# IoTMainBoard.net
KiCad netlist of a schematic drawn in Altium Designer
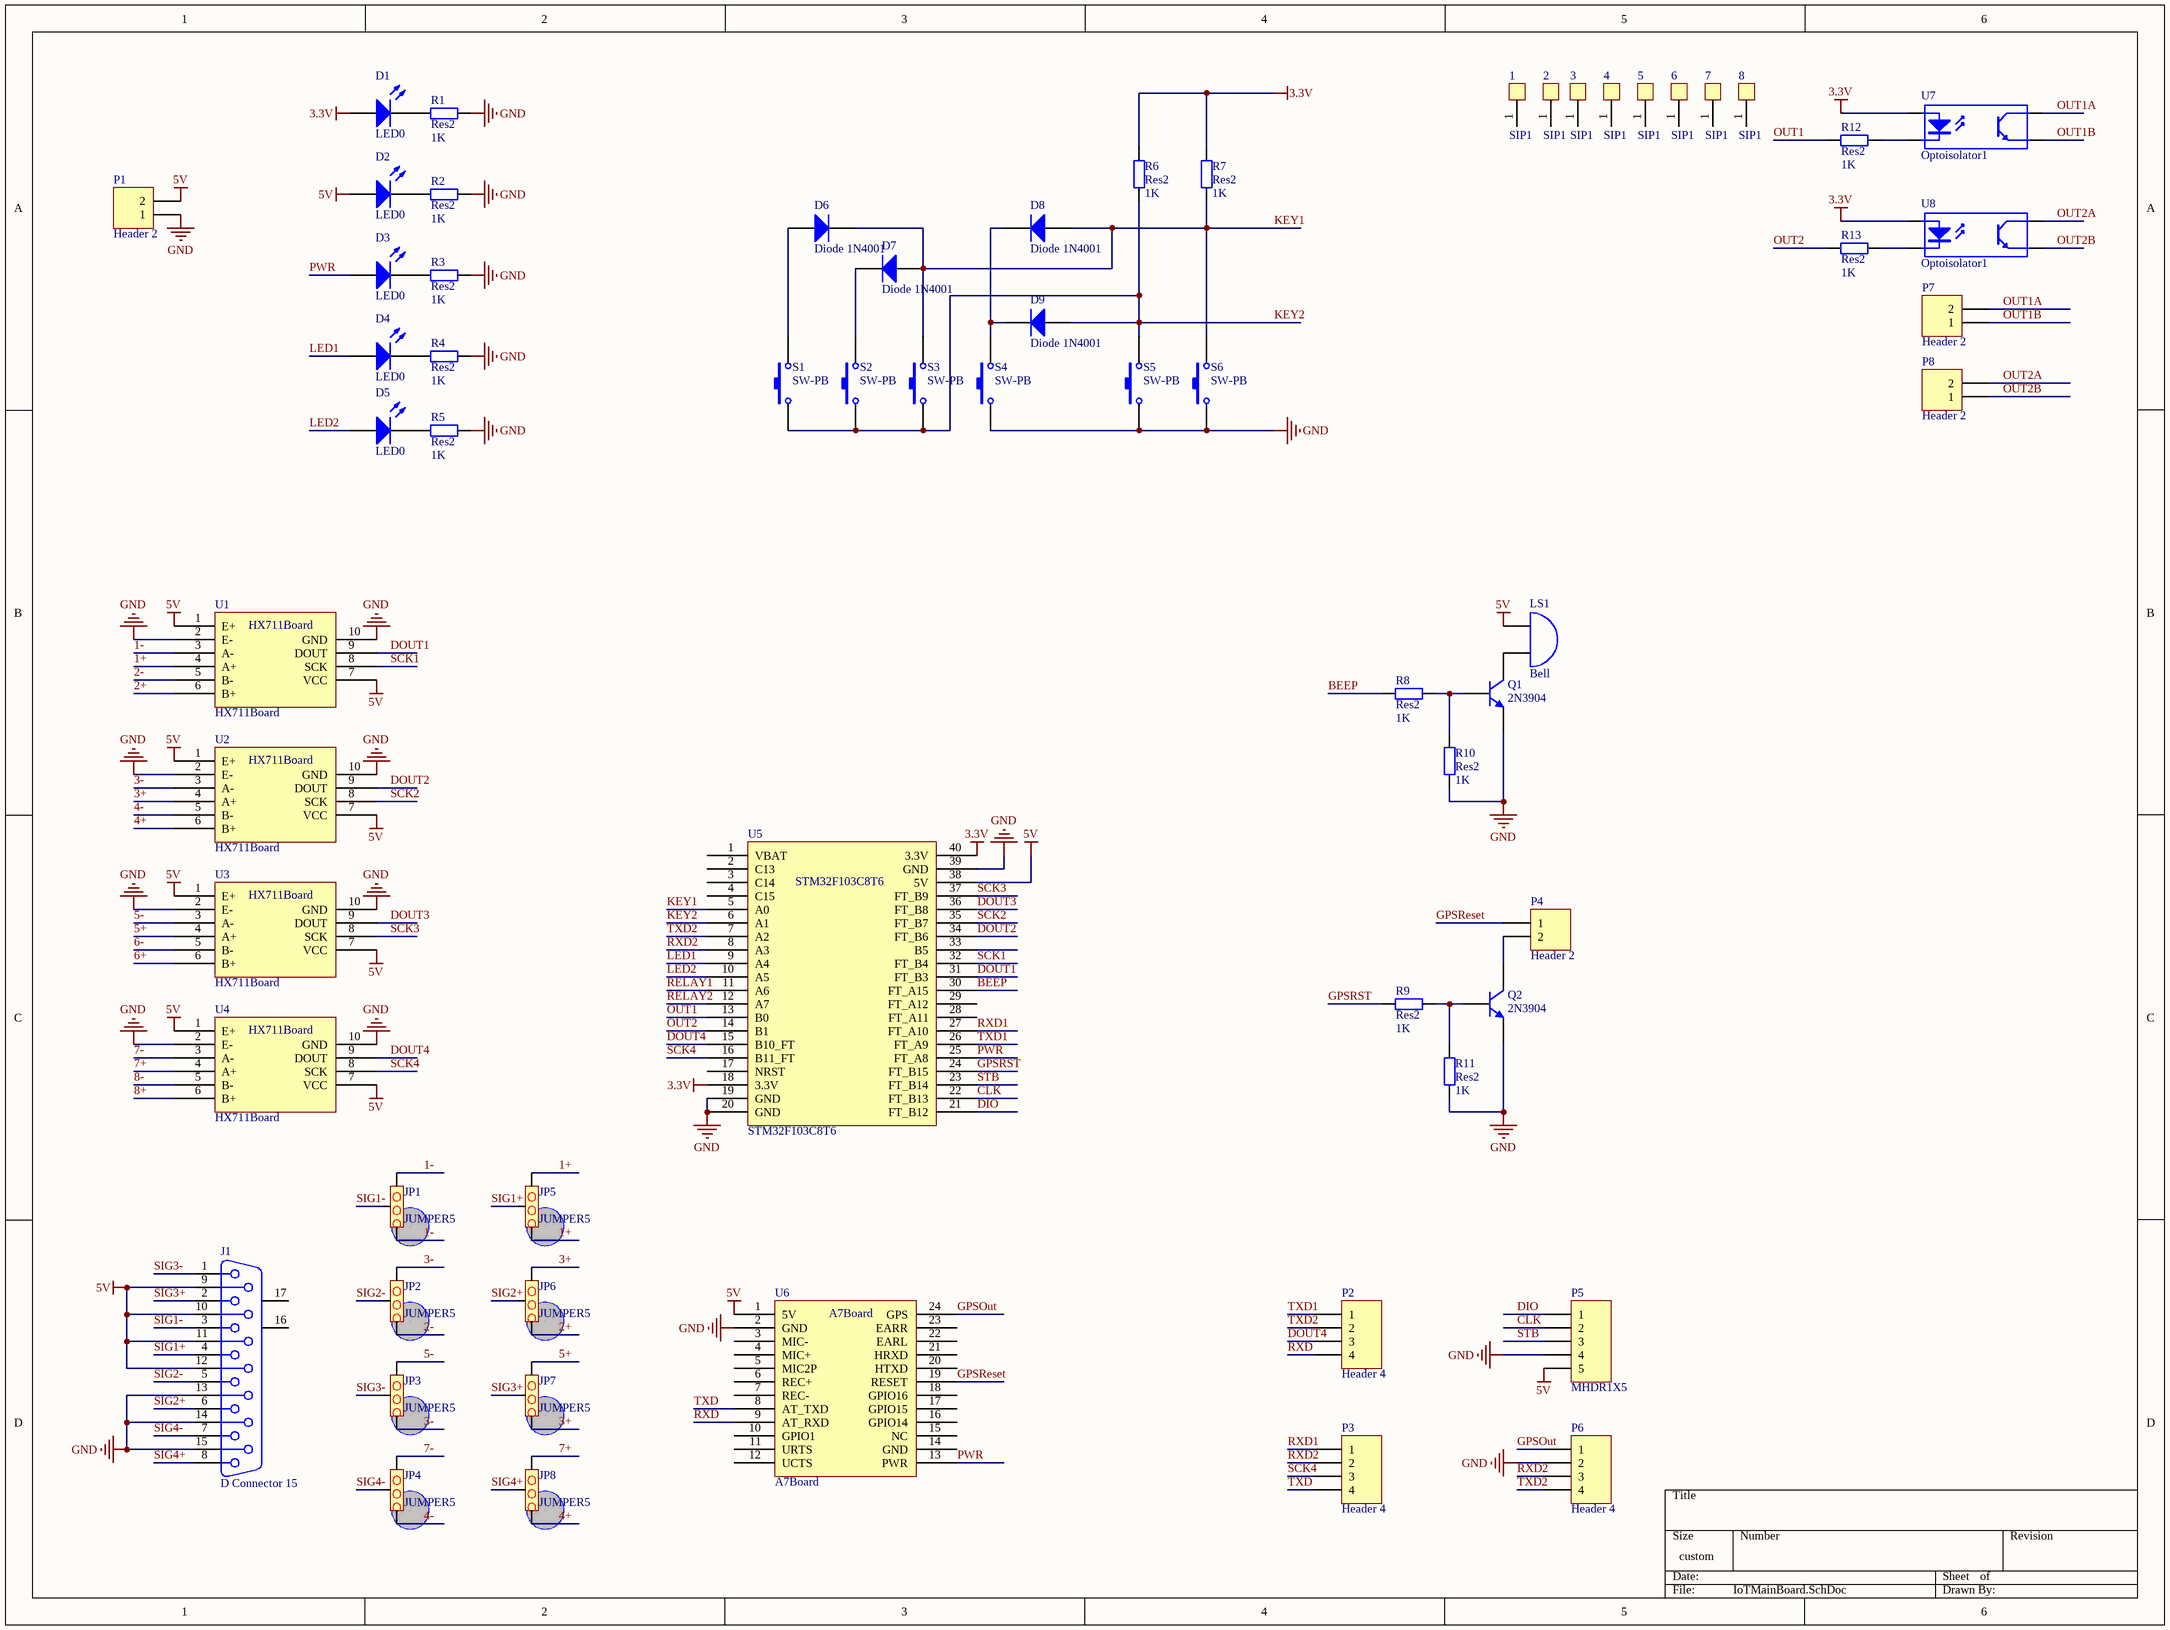
[diagram p0: IoTMainBoard.SchDoc]

(export (version "E")
  (design (tool "Eeschema 10.0.6"))
  (components
    (comp (ref "1")
      (value "SIP1")
      (footprint "hole")
      (description "Variable Resistor")
      (fields (field (name "PUBLISHER") "Altium Limited"))
      (libsource (lib "jointbar") (part "SIP1"))
    )
    (comp (ref "2")
      (value "SIP1")
      (footprint "hole")
      (description "Variable Resistor")
      (fields (field (name "PUBLISHER") "Altium Limited"))
      (libsource (lib "jointbar") (part "SIP1"))
    )
    (comp (ref "3")
      (value "SIP1")
      (footprint "hole")
      (description "Variable Resistor")
      (fields (field (name "PUBLISHER") "Altium Limited"))
      (libsource (lib "jointbar") (part "SIP1"))
    )
    (comp (ref "4")
      (value "SIP1")
      (footprint "hole")
      (description "Variable Resistor")
      (fields (field (name "PUBLISHER") "Altium Limited"))
      (libsource (lib "jointbar") (part "SIP1"))
    )
    (comp (ref "5")
      (value "SIP1")
      (footprint "hole")
      (description "Variable Resistor")
      (fields (field (name "PUBLISHER") "Altium Limited"))
      (libsource (lib "jointbar") (part "SIP1"))
    )
    (comp (ref "6")
      (value "SIP1")
      (footprint "hole")
      (description "Variable Resistor")
      (fields (field (name "PUBLISHER") "Altium Limited"))
      (libsource (lib "jointbar") (part "SIP1"))
    )
    (comp (ref "7")
      (value "SIP1")
      (footprint "hole")
      (description "Variable Resistor")
      (fields (field (name "PUBLISHER") "Altium Limited"))
      (libsource (lib "jointbar") (part "SIP1"))
    )
    (comp (ref "8")
      (value "SIP1")
      (footprint "hole")
      (description "Variable Resistor")
      (fields (field (name "PUBLISHER") "Altium Limited"))
      (libsource (lib "jointbar") (part "SIP1"))
    )
    (comp (ref "D1")
      (value "LED0")
      (footprint "LED0")
      (description "Typical INFRARED GaAs LED")
      (fields (field (name "PUBLISHER") "Altium Limited"))
      (libsource (lib "Miscellaneous Devices") (part "LED0"))
    )
    (comp (ref "D2")
      (value "LED0")
      (footprint "LED0")
      (description "Typical INFRARED GaAs LED")
      (fields (field (name "PUBLISHER") "Altium Limited"))
      (libsource (lib "Miscellaneous Devices") (part "LED0"))
    )
    (comp (ref "D3")
      (value "LED0")
      (footprint "LED0")
      (description "Typical INFRARED GaAs LED")
      (fields (field (name "PUBLISHER") "Altium Limited"))
      (libsource (lib "Miscellaneous Devices") (part "LED0"))
    )
    (comp (ref "D4")
      (value "LED0")
      (footprint "LED0")
      (description "Typical INFRARED GaAs LED")
      (fields (field (name "PUBLISHER") "Altium Limited"))
      (libsource (lib "Miscellaneous Devices") (part "LED0"))
    )
    (comp (ref "D5")
      (value "LED0")
      (footprint "LED0")
      (description "Typical INFRARED GaAs LED")
      (fields (field (name "PUBLISHER") "Altium Limited"))
      (libsource (lib "Miscellaneous Devices") (part "LED0"))
    )
    (comp (ref "D6")
      (value "Diode 1N4001")
      (footprint "1N4148")
      (description "1 Amp General Purpose Rectifier")
      (fields (field (name "PUBLISHER") "Altium Limited"))
      (libsource (lib "Miscellaneous Devices") (part "Diode 1N4001"))
    )
    (comp (ref "D7")
      (value "Diode 1N4001")
      (footprint "1N4148")
      (description "1 Amp General Purpose Rectifier")
      (fields (field (name "PUBLISHER") "Altium Limited"))
      (libsource (lib "Miscellaneous Devices") (part "Diode 1N4001"))
    )
    (comp (ref "D8")
      (value "Diode 1N4001")
      (footprint "1N4148")
      (description "1 Amp General Purpose Rectifier")
      (fields (field (name "PUBLISHER") "Altium Limited"))
      (libsource (lib "Miscellaneous Devices") (part "Diode 1N4001"))
    )
    (comp (ref "D9")
      (value "Diode 1N4001")
      (footprint "1N4148")
      (description "1 Amp General Purpose Rectifier")
      (fields (field (name "PUBLISHER") "Altium Limited"))
      (libsource (lib "Miscellaneous Devices") (part "Diode 1N4001"))
    )
    (comp (ref "J1")
      (value "D Connector 15")
      (footprint "DB15F_DB")
      (description "Receptacle Assembly, 15 Position, Right Angle")
      (fields (field (name "PUBLISHER") "Altium Limited"))
      (libsource (lib "Miscellaneous Connectors") (part "D Connector 15"))
    )
    (comp (ref "JP1") (value "JUMPER5") (footprint "CON3") (libsource (lib "jointbar") (part "JUMPER5")))
    (comp (ref "JP2") (value "JUMPER5") (footprint "CON3") (libsource (lib "jointbar") (part "JUMPER5")))
    (comp (ref "JP3") (value "JUMPER5") (footprint "CON3") (libsource (lib "jointbar") (part "JUMPER5")))
    (comp (ref "JP4") (value "JUMPER5") (footprint "CON3") (libsource (lib "jointbar") (part "JUMPER5")))
    (comp (ref "JP5") (value "JUMPER5") (footprint "CON3") (libsource (lib "jointbar") (part "JUMPER5")))
    (comp (ref "JP6") (value "JUMPER5") (footprint "CON3") (libsource (lib "jointbar") (part "JUMPER5")))
    (comp (ref "JP7") (value "JUMPER5") (footprint "CON3") (libsource (lib "jointbar") (part "JUMPER5")))
    (comp (ref "JP8") (value "JUMPER5") (footprint "CON3") (libsource (lib "jointbar") (part "JUMPER5")))
    (comp (ref "LS1")
      (value "Bell")
      (footprint "BEEP")
      (description "Electrical Bell")
      (fields (field (name "PUBLISHER") "Altium Limited"))
      (libsource (lib "Miscellaneous Devices") (part "Bell"))
    )
    (comp (ref "P1")
      (value "Header 2")
      (footprint "Power2")
      (description "Header, 2-Pin")
      (fields (field (name "PUBLISHER") "Altium Limited"))
      (libsource (lib "Miscellaneous Connectors") (part "Header 2"))
    )
    (comp (ref "P2")
      (value "Header 4")
      (footprint "JUMP3")
      (description "Header, 4-Pin")
      (fields (field (name "PUBLISHER") "Altium Limited"))
      (libsource (lib "Miscellaneous Connectors") (part "Header 4"))
    )
    (comp (ref "P3")
      (value "Header 4")
      (footprint "JUMP3")
      (description "Header, 4-Pin")
      (fields (field (name "PUBLISHER") "Altium Limited"))
      (libsource (lib "Miscellaneous Connectors") (part "Header 4"))
    )
    (comp (ref "P4")
      (value "Header 2")
      (footprint "HDR1X2")
      (description "Header, 2-Pin")
      (fields (field (name "PUBLISHER") "Altium Limited"))
      (libsource (lib "") (part "Header 2_1"))
    )
    (comp (ref "P5")
      (value "MHDR1X5")
      (footprint "HDR1X5")
      (description "Header, 5-Pin")
      (fields (field (name "PUBLISHER") "Altium Limited"))
      (libsource (lib "Miscellaneous Connectors") (part "MHDR1X5"))
    )
    (comp (ref "P6")
      (value "Header 4")
      (footprint "HDR1X4")
      (description "Header, 4-Pin")
      (fields (field (name "PUBLISHER") "Altium Limited"))
      (libsource (lib "Miscellaneous Connectors") (part "Header 4"))
    )
    (comp (ref "P7")
      (value "Header 2")
      (footprint "HDR1X2")
      (description "Header, 2-Pin")
      (fields (field (name "PUBLISHER") "Altium Limited"))
      (libsource (lib "Miscellaneous Connectors") (part "Header 2"))
    )
    (comp (ref "P8")
      (value "Header 2")
      (footprint "HDR1X2")
      (description "Header, 2-Pin")
      (fields (field (name "PUBLISHER") "Altium Limited"))
      (libsource (lib "Miscellaneous Connectors") (part "Header 2"))
    )
    (comp (ref "Q1")
      (value "2N3904")
      (footprint "SOT-23")
      (description "NPN General Purpose Amplifier")
      (fields (field (name "PUBLISHER") "Altium Limited"))
      (libsource (lib "Miscellaneous Devices") (part "2N3904"))
    )
    (comp (ref "Q2")
      (value "2N3904")
      (footprint "SOT-23")
      (description "NPN General Purpose Amplifier")
      (fields (field (name "PUBLISHER") "Altium Limited"))
      (libsource (lib "Miscellaneous Devices") (part "2N3904"))
    )
    (comp (ref "R1")
      (value "Res2")
      (footprint "0805")
      (description "Resistor")
      (fields (field (name "ALTIUM_VALUE") "1K") (field (name "PUBLISHER") "Altium Limited"))
      (libsource (lib "") (part "Res2_2"))
    )
    (comp (ref "R2")
      (value "Res2")
      (footprint "0805")
      (description "Resistor")
      (fields (field (name "ALTIUM_VALUE") "1K") (field (name "PUBLISHER") "Altium Limited"))
      (libsource (lib "") (part "Res2_2"))
    )
    (comp (ref "R3")
      (value "Res2")
      (footprint "0805")
      (description "Resistor")
      (fields (field (name "ALTIUM_VALUE") "1K") (field (name "PUBLISHER") "Altium Limited"))
      (libsource (lib "") (part "Res2_2"))
    )
    (comp (ref "R4")
      (value "Res2")
      (footprint "0805")
      (description "Resistor")
      (fields (field (name "ALTIUM_VALUE") "1K") (field (name "PUBLISHER") "Altium Limited"))
      (libsource (lib "") (part "Res2_2"))
    )
    (comp (ref "R5")
      (value "Res2")
      (footprint "0805")
      (description "Resistor")
      (fields (field (name "ALTIUM_VALUE") "1K") (field (name "PUBLISHER") "Altium Limited"))
      (libsource (lib "") (part "Res2_2"))
    )
    (comp (ref "R6")
      (value "Res2")
      (footprint "0805")
      (description "Resistor")
      (fields (field (name "ALTIUM_VALUE") "1K") (field (name "PUBLISHER") "Altium Limited"))
      (libsource (lib "Miscellaneous Devices") (part "Res2"))
    )
    (comp (ref "R7")
      (value "Res2")
      (footprint "0805")
      (description "Resistor")
      (fields (field (name "ALTIUM_VALUE") "1K") (field (name "PUBLISHER") "Altium Limited"))
      (libsource (lib "Miscellaneous Devices") (part "Res2"))
    )
    (comp (ref "R8")
      (value "Res2")
      (footprint "0805")
      (description "Resistor")
      (fields (field (name "ALTIUM_VALUE") "1K") (field (name "PUBLISHER") "Altium Limited"))
      (libsource (lib "") (part "Res2_2"))
    )
    (comp (ref "R9")
      (value "Res2")
      (footprint "0805")
      (description "Resistor")
      (fields (field (name "ALTIUM_VALUE") "1K") (field (name "PUBLISHER") "Altium Limited"))
      (libsource (lib "") (part "Res2_2"))
    )
    (comp (ref "R10")
      (value "Res2")
      (footprint "0805")
      (description "Resistor")
      (fields (field (name "ALTIUM_VALUE") "1K") (field (name "PUBLISHER") "Altium Limited"))
      (libsource (lib "") (part "Res2_1"))
    )
    (comp (ref "R11")
      (value "Res2")
      (footprint "0805")
      (description "Resistor")
      (fields (field (name "ALTIUM_VALUE") "1K") (field (name "PUBLISHER") "Altium Limited"))
      (libsource (lib "") (part "Res2_1"))
    )
    (comp (ref "R12")
      (value "Res2")
      (footprint "0805")
      (description "Resistor")
      (fields (field (name "ALTIUM_VALUE") "1K") (field (name "PUBLISHER") "Altium Limited"))
      (libsource (lib "") (part "Res2_3"))
    )
    (comp (ref "R13")
      (value "Res2")
      (footprint "0805")
      (description "Resistor")
      (fields (field (name "ALTIUM_VALUE") "1K") (field (name "PUBLISHER") "Altium Limited"))
      (libsource (lib "") (part "Res2_3"))
    )
    (comp (ref "S1")
      (value "SW-PB")
      (footprint "KEY1")
      (description "Switch")
      (fields (field (name "PUBLISHER") "Altium Limited"))
      (libsource (lib "Miscellaneous Devices") (part "SW-PB"))
    )
    (comp (ref "S2")
      (value "SW-PB")
      (footprint "KEY1")
      (description "Switch")
      (fields (field (name "PUBLISHER") "Altium Limited"))
      (libsource (lib "Miscellaneous Devices") (part "SW-PB"))
    )
    (comp (ref "S3")
      (value "SW-PB")
      (footprint "KEY1")
      (description "Switch")
      (fields (field (name "PUBLISHER") "Altium Limited"))
      (libsource (lib "Miscellaneous Devices") (part "SW-PB"))
    )
    (comp (ref "S4")
      (value "SW-PB")
      (footprint "KEY1")
      (description "Switch")
      (fields (field (name "PUBLISHER") "Altium Limited"))
      (libsource (lib "Miscellaneous Devices") (part "SW-PB"))
    )
    (comp (ref "S5")
      (value "SW-PB")
      (footprint "KEY1")
      (description "Switch")
      (fields (field (name "PUBLISHER") "Altium Limited"))
      (libsource (lib "Miscellaneous Devices") (part "SW-PB"))
    )
    (comp (ref "S6")
      (value "SW-PB")
      (footprint "KEY1")
      (description "Switch")
      (fields (field (name "PUBLISHER") "Altium Limited"))
      (libsource (lib "Miscellaneous Devices") (part "SW-PB"))
    )
    (comp (ref "U1") (value "HX711Board") (footprint "HX711") (libsource (lib "zhaichl") (part "HX711Board")))
    (comp (ref "U2") (value "HX711Board") (footprint "HX711") (libsource (lib "zhaichl") (part "HX711Board")))
    (comp (ref "U3") (value "HX711Board") (footprint "HX711") (libsource (lib "zhaichl") (part "HX711Board")))
    (comp (ref "U4") (value "HX711Board") (footprint "HX711") (libsource (lib "zhaichl") (part "HX711Board")))
    (comp (ref "U5")
      (value "STM32F103C8T6")
      (footprint "STM32F103C8T6")
      (description "STM32F103C8T6 Board")
      (libsource (lib "zhaichl") (part "STM32F103C8T6"))
    )
    (comp (ref "U6") (value "A7Board") (footprint "A7Board") (libsource (lib "zhaichl") (part "A7Board")))
    (comp (ref "U7")
      (value "Optoisolator1")
      (footprint "SOP4")
      (description "4-Pin Phototransistor Optocoupler")
      (fields (field (name "PUBLISHER") "Altium Limited"))
      (libsource (lib "Miscellaneous Devices") (part "Optoisolator1"))
    )
    (comp (ref "U8")
      (value "Optoisolator1")
      (footprint "SOP4")
      (description "4-Pin Phototransistor Optocoupler")
      (fields (field (name "PUBLISHER") "Altium Limited"))
      (libsource (lib "Miscellaneous Devices") (part "Optoisolator1"))
    )
  )
  (nets
    (net (code "1") (name "/1+") (class "Default")
      (node (ref "JP5") (pin "1") (pinfunction "1_1") (pintype "passive"))
      (node (ref "JP5") (pin "3") (pinfunction "3_3") (pintype "passive"))
      (node (ref "U1") (pin "4") (pinfunction "A+_4") (pintype "passive"))
    )
    (net (code "2") (name "/1-") (class "Default")
      (node (ref "JP1") (pin "1") (pinfunction "1_1") (pintype "passive"))
      (node (ref "JP1") (pin "3") (pinfunction "3_3") (pintype "passive"))
      (node (ref "U1") (pin "3") (pinfunction "A-_3") (pintype "passive"))
    )
    (net (code "3") (name "/2+") (class "Default")
      (node (ref "JP6") (pin "1") (pinfunction "1_1") (pintype "passive"))
      (node (ref "U1") (pin "6") (pinfunction "B+_6") (pintype "passive"))
    )
    (net (code "4") (name "/2-") (class "Default")
      (node (ref "JP2") (pin "1") (pinfunction "1_1") (pintype "passive"))
      (node (ref "U1") (pin "5") (pinfunction "B-_5") (pintype "passive"))
    )
    (net (code "5") (name "/3+") (class "Default")
      (node (ref "JP6") (pin "3") (pinfunction "3_3") (pintype "passive"))
      (node (ref "JP7") (pin "1") (pinfunction "1_1") (pintype "passive"))
      (node (ref "U2") (pin "4") (pinfunction "A+_4") (pintype "passive"))
    )
    (net (code "6") (name "/3-") (class "Default")
      (node (ref "JP2") (pin "3") (pinfunction "3_3") (pintype "passive"))
      (node (ref "JP3") (pin "1") (pinfunction "1_1") (pintype "passive"))
      (node (ref "U2") (pin "3") (pinfunction "A-_3") (pintype "passive"))
    )
    (net (code "7") (name "/4+") (class "Default")
      (node (ref "JP8") (pin "1") (pinfunction "1_1") (pintype "passive"))
      (node (ref "U2") (pin "6") (pinfunction "B+_6") (pintype "passive"))
    )
    (net (code "8") (name "/4-") (class "Default")
      (node (ref "JP4") (pin "1") (pinfunction "1_1") (pintype "passive"))
      (node (ref "U2") (pin "5") (pinfunction "B-_5") (pintype "passive"))
    )
    (net (code "9") (name "/5+") (class "Default")
      (node (ref "JP7") (pin "3") (pinfunction "3_3") (pintype "passive"))
      (node (ref "U3") (pin "4") (pinfunction "A+_4") (pintype "passive"))
    )
    (net (code "10") (name "/5-") (class "Default")
      (node (ref "JP3") (pin "3") (pinfunction "3_3") (pintype "passive"))
      (node (ref "U3") (pin "3") (pinfunction "A-_3") (pintype "passive"))
    )
    (net (code "11") (name "/6+") (class "Default")
      (node (ref "U3") (pin "6") (pinfunction "B+_6") (pintype "passive"))
    )
    (net (code "12") (name "/6-") (class "Default")
      (node (ref "U3") (pin "5") (pinfunction "B-_5") (pintype "passive"))
    )
    (net (code "13") (name "/7+") (class "Default")
      (node (ref "JP8") (pin "3") (pinfunction "3_3") (pintype "passive"))
      (node (ref "U4") (pin "4") (pinfunction "A+_4") (pintype "passive"))
    )
    (net (code "14") (name "/7-") (class "Default")
      (node (ref "JP4") (pin "3") (pinfunction "3_3") (pintype "passive"))
      (node (ref "U4") (pin "3") (pinfunction "A-_3") (pintype "passive"))
    )
    (net (code "15") (name "/8+") (class "Default")
      (node (ref "U4") (pin "6") (pinfunction "B+_6") (pintype "passive"))
    )
    (net (code "16") (name "/8-") (class "Default")
      (node (ref "U4") (pin "5") (pinfunction "B-_5") (pintype "passive"))
    )
    (net (code "17") (name "/BEEP") (class "Default")
      (node (ref "R8") (pin "2") (pinfunction "2_2") (pintype "passive"))
      (node (ref "U5") (pin "30") (pinfunction "FT_A15_30") (pintype "passive"))
    )
    (net (code "18") (name "/CLK") (class "Default")
      (node (ref "P5") (pin "2") (pinfunction "2_2") (pintype "passive"))
      (node (ref "U5") (pin "22") (pinfunction "FT_B13_22") (pintype "passive"))
    )
    (net (code "19") (name "/DIO") (class "Default")
      (node (ref "P5") (pin "1") (pinfunction "1_1") (pintype "passive"))
      (node (ref "U5") (pin "21") (pinfunction "FT_B12_21") (pintype "passive"))
    )
    (net (code "20") (name "/DOUT1") (class "Default")
      (node (ref "U1") (pin "9") (pinfunction "DOUT_9") (pintype "passive"))
      (node (ref "U5") (pin "31") (pinfunction "FT_B3_31") (pintype "passive"))
    )
    (net (code "21") (name "/DOUT2") (class "Default")
      (node (ref "U2") (pin "9") (pinfunction "DOUT_9") (pintype "passive"))
      (node (ref "U5") (pin "34") (pinfunction "FT_B6_34") (pintype "passive"))
    )
    (net (code "22") (name "/DOUT3") (class "Default")
      (node (ref "U3") (pin "9") (pinfunction "DOUT_9") (pintype "passive"))
      (node (ref "U5") (pin "36") (pinfunction "FT_B8_36") (pintype "passive"))
    )
    (net (code "23") (name "/DOUT4") (class "Default")
      (node (ref "P2") (pin "3") (pinfunction "3_3") (pintype "passive"))
      (node (ref "U4") (pin "9") (pinfunction "DOUT_9") (pintype "passive"))
      (node (ref "U5") (pin "15") (pinfunction "B10_FT_15") (pintype "passive"))
    )
    (net (code "24") (name "/GPSOut") (class "Default")
      (node (ref "P6") (pin "1") (pinfunction "1_1") (pintype "passive"))
      (node (ref "U6") (pin "24") (pinfunction "GPS_24") (pintype "passive"))
    )
    (net (code "25") (name "/GPSRST") (class "Default")
      (node (ref "R9") (pin "2") (pinfunction "2_2") (pintype "passive"))
      (node (ref "U5") (pin "24") (pinfunction "FT_B15_24") (pintype "passive"))
    )
    (net (code "26") (name "/GPSReset") (class "Default")
      (node (ref "P4") (pin "1") (pinfunction "1_1") (pintype "passive"))
      (node (ref "U6") (pin "19") (pinfunction "RESET_19") (pintype "passive"))
    )
    (net (code "27") (name "/KEY1") (class "Default")
      (node (ref "D6") (pin "2") (pinfunction "K_2") (pintype "passive"))
      (node (ref "D7") (pin "1") (pinfunction "A_1") (pintype "passive"))
      (node (ref "D8") (pin "1") (pinfunction "A_1") (pintype "passive"))
      (node (ref "R7") (pin "1") (pinfunction "1_1") (pintype "passive"))
      (node (ref "S3") (pin "2") (pinfunction "2_2") (pintype "passive"))
      (node (ref "S6") (pin "2") (pinfunction "2_2") (pintype "passive"))
      (node (ref "U5") (pin "5") (pinfunction "A0_5") (pintype "passive"))
    )
    (net (code "28") (name "/KEY2") (class "Default")
      (node (ref "D9") (pin "1") (pinfunction "A_1") (pintype "passive"))
      (node (ref "R6") (pin "1") (pinfunction "1_1") (pintype "passive"))
      (node (ref "S1") (pin "1") (pinfunction "1_1") (pintype "passive"))
      (node (ref "S2") (pin "1") (pinfunction "1_1") (pintype "passive"))
      (node (ref "S3") (pin "1") (pinfunction "1_1") (pintype "passive"))
      (node (ref "S5") (pin "2") (pinfunction "2_2") (pintype "passive"))
      (node (ref "U5") (pin "6") (pinfunction "A1_6") (pintype "passive"))
    )
    (net (code "29") (name "/LED1") (class "Default")
      (node (ref "D4") (pin "1") (pinfunction "A_1") (pintype "passive"))
      (node (ref "U5") (pin "9") (pinfunction "A4_9") (pintype "passive"))
    )
    (net (code "30") (name "/LED2") (class "Default")
      (node (ref "D5") (pin "1") (pinfunction "A_1") (pintype "passive"))
      (node (ref "U5") (pin "10") (pinfunction "A5_10") (pintype "passive"))
    )
    (net (code "31") (name "/OUT1") (class "Default")
      (node (ref "R12") (pin "1") (pinfunction "1_1") (pintype "passive"))
      (node (ref "U5") (pin "13") (pinfunction "B0_13") (pintype "passive"))
    )
    (net (code "32") (name "/OUT1A") (class "Default")
      (node (ref "P7") (pin "2") (pinfunction "2_2") (pintype "passive"))
      (node (ref "U7") (pin "4") (pinfunction "C_4") (pintype "passive"))
    )
    (net (code "33") (name "/OUT1B") (class "Default")
      (node (ref "P7") (pin "1") (pinfunction "1_1") (pintype "passive"))
      (node (ref "U7") (pin "3") (pinfunction "E_3") (pintype "passive"))
    )
    (net (code "34") (name "/OUT2") (class "Default")
      (node (ref "R13") (pin "1") (pinfunction "1_1") (pintype "passive"))
      (node (ref "U5") (pin "14") (pinfunction "B1_14") (pintype "passive"))
    )
    (net (code "35") (name "/OUT2A") (class "Default")
      (node (ref "P8") (pin "2") (pinfunction "2_2") (pintype "passive"))
      (node (ref "U8") (pin "4") (pinfunction "C_4") (pintype "passive"))
    )
    (net (code "36") (name "/OUT2B") (class "Default")
      (node (ref "P8") (pin "1") (pinfunction "1_1") (pintype "passive"))
      (node (ref "U8") (pin "3") (pinfunction "E_3") (pintype "passive"))
    )
    (net (code "37") (name "/PWR") (class "Default")
      (node (ref "D3") (pin "1") (pinfunction "A_1") (pintype "passive"))
      (node (ref "U5") (pin "25") (pinfunction "FT_A8_25") (pintype "passive"))
      (node (ref "U6") (pin "13") (pinfunction "PWR_13") (pintype "passive"))
    )
    (net (code "38") (name "/RELAY1") (class "Default")
      (node (ref "U5") (pin "11") (pinfunction "A6_11") (pintype "passive"))
    )
    (net (code "39") (name "/RELAY2") (class "Default")
      (node (ref "U5") (pin "12") (pinfunction "A7_12") (pintype "passive"))
    )
    (net (code "40") (name "/RXD") (class "Default")
      (node (ref "P2") (pin "4") (pinfunction "4_4") (pintype "passive"))
      (node (ref "U6") (pin "9") (pinfunction "AT_RXD_9") (pintype "passive"))
    )
    (net (code "41") (name "/RXD1") (class "Default")
      (node (ref "P3") (pin "1") (pinfunction "1_1") (pintype "passive"))
      (node (ref "U5") (pin "27") (pinfunction "FT_A10_27") (pintype "passive"))
    )
    (net (code "42") (name "/RXD2") (class "Default")
      (node (ref "P3") (pin "2") (pinfunction "2_2") (pintype "passive"))
      (node (ref "P6") (pin "3") (pinfunction "3_3") (pintype "passive"))
      (node (ref "U5") (pin "8") (pinfunction "A3_8") (pintype "passive"))
    )
    (net (code "43") (name "/SCK1") (class "Default")
      (node (ref "U1") (pin "8") (pinfunction "SCK_8") (pintype "passive"))
      (node (ref "U5") (pin "32") (pinfunction "FT_B4_32") (pintype "passive"))
    )
    (net (code "44") (name "/SCK2") (class "Default")
      (node (ref "U2") (pin "8") (pinfunction "SCK_8") (pintype "passive"))
      (node (ref "U5") (pin "35") (pinfunction "FT_B7_35") (pintype "passive"))
    )
    (net (code "45") (name "/SCK3") (class "Default")
      (node (ref "U3") (pin "8") (pinfunction "SCK_8") (pintype "passive"))
      (node (ref "U5") (pin "37") (pinfunction "FT_B9_37") (pintype "passive"))
    )
    (net (code "46") (name "/SCK4") (class "Default")
      (node (ref "P3") (pin "3") (pinfunction "3_3") (pintype "passive"))
      (node (ref "U4") (pin "8") (pinfunction "SCK_8") (pintype "passive"))
      (node (ref "U5") (pin "16") (pinfunction "B11_FT_16") (pintype "passive"))
    )
    (net (code "47") (name "/SIG1+") (class "Default")
      (node (ref "J1") (pin "4") (pinfunction "4_4") (pintype "passive"))
      (node (ref "JP5") (pin "2") (pinfunction "2_2") (pintype "passive"))
    )
    (net (code "48") (name "/SIG1-") (class "Default")
      (node (ref "J1") (pin "3") (pinfunction "3_3") (pintype "passive"))
      (node (ref "JP1") (pin "2") (pinfunction "2_2") (pintype "passive"))
    )
    (net (code "49") (name "/SIG2+") (class "Default")
      (node (ref "J1") (pin "6") (pinfunction "6_6") (pintype "passive"))
      (node (ref "JP6") (pin "2") (pinfunction "2_2") (pintype "passive"))
    )
    (net (code "50") (name "/SIG2-") (class "Default")
      (node (ref "J1") (pin "5") (pinfunction "5_5") (pintype "passive"))
      (node (ref "JP2") (pin "2") (pinfunction "2_2") (pintype "passive"))
    )
    (net (code "51") (name "/SIG3+") (class "Default")
      (node (ref "J1") (pin "2") (pinfunction "2_2") (pintype "passive"))
      (node (ref "JP7") (pin "2") (pinfunction "2_2") (pintype "passive"))
    )
    (net (code "52") (name "/SIG3-") (class "Default")
      (node (ref "J1") (pin "1") (pinfunction "1_1") (pintype "passive"))
      (node (ref "JP3") (pin "2") (pinfunction "2_2") (pintype "passive"))
    )
    (net (code "53") (name "/SIG4+") (class "Default")
      (node (ref "J1") (pin "8") (pinfunction "8_8") (pintype "passive"))
      (node (ref "JP8") (pin "2") (pinfunction "2_2") (pintype "passive"))
    )
    (net (code "54") (name "/SIG4-") (class "Default")
      (node (ref "J1") (pin "7") (pinfunction "7_7") (pintype "passive"))
      (node (ref "JP4") (pin "2") (pinfunction "2_2") (pintype "passive"))
    )
    (net (code "55") (name "/STB") (class "Default")
      (node (ref "P5") (pin "3") (pinfunction "3_3") (pintype "passive"))
      (node (ref "U5") (pin "23") (pinfunction "FT_B14_23") (pintype "passive"))
    )
    (net (code "56") (name "/TXD") (class "Default")
      (node (ref "P3") (pin "4") (pinfunction "4_4") (pintype "passive"))
      (node (ref "U6") (pin "8") (pinfunction "AT_TXD_8") (pintype "passive"))
    )
    (net (code "57") (name "/TXD1") (class "Default")
      (node (ref "P2") (pin "1") (pinfunction "1_1") (pintype "passive"))
      (node (ref "U5") (pin "26") (pinfunction "FT_A9_26") (pintype "passive"))
    )
    (net (code "58") (name "/TXD2") (class "Default")
      (node (ref "P2") (pin "2") (pinfunction "2_2") (pintype "passive"))
      (node (ref "P6") (pin "4") (pinfunction "4_4") (pintype "passive"))
      (node (ref "U5") (pin "7") (pinfunction "A2_7") (pintype "passive"))
    )
    (net (code "59") (name "3.3V") (class "Default")
      (node (ref "D1") (pin "1") (pinfunction "A_1") (pintype "passive"))
      (node (ref "R6") (pin "2") (pinfunction "2_2") (pintype "passive"))
      (node (ref "R7") (pin "2") (pinfunction "2_2") (pintype "passive"))
      (node (ref "U5") (pin "18") (pinfunction "3.3V_18") (pintype "passive"))
      (node (ref "U5") (pin "40") (pinfunction "3.3V_40") (pintype "passive"))
      (node (ref "U7") (pin "1") (pinfunction "A_1") (pintype "passive"))
      (node (ref "U8") (pin "1") (pinfunction "A_1") (pintype "passive"))
    )
    (net (code "60") (name "5V") (class "Default")
      (node (ref "D2") (pin "1") (pinfunction "A_1") (pintype "passive"))
      (node (ref "J1") (pin "10") (pinfunction "10_10") (pintype "passive"))
      (node (ref "J1") (pin "11") (pinfunction "11_11") (pintype "passive"))
      (node (ref "J1") (pin "12") (pinfunction "12_12") (pintype "passive"))
      (node (ref "J1") (pin "9") (pinfunction "9_9") (pintype "passive"))
      (node (ref "LS1") (pin "1") (pinfunction "A_1") (pintype "passive"))
      (node (ref "P1") (pin "2") (pinfunction "2_2") (pintype "passive"))
      (node (ref "P5") (pin "5") (pinfunction "5_5") (pintype "passive"))
      (node (ref "U1") (pin "1") (pinfunction "E+_1") (pintype "passive"))
      (node (ref "U1") (pin "7") (pinfunction "VCC_7") (pintype "passive"))
      (node (ref "U2") (pin "1") (pinfunction "E+_1") (pintype "passive"))
      (node (ref "U2") (pin "7") (pinfunction "VCC_7") (pintype "passive"))
      (node (ref "U3") (pin "1") (pinfunction "E+_1") (pintype "passive"))
      (node (ref "U3") (pin "7") (pinfunction "VCC_7") (pintype "passive"))
      (node (ref "U4") (pin "1") (pinfunction "E+_1") (pintype "passive"))
      (node (ref "U4") (pin "7") (pinfunction "VCC_7") (pintype "passive"))
      (node (ref "U5") (pin "38") (pinfunction "5V_38") (pintype "passive"))
      (node (ref "U6") (pin "1") (pinfunction "5V_1") (pintype "passive"))
    )
    (net (code "61") (name "GND") (class "Default")
      (node (ref "J1") (pin "13") (pinfunction "13_13") (pintype "passive"))
      (node (ref "J1") (pin "14") (pinfunction "14_14") (pintype "passive"))
      (node (ref "J1") (pin "15") (pinfunction "15_15") (pintype "passive"))
      (node (ref "P1") (pin "1") (pinfunction "1_1") (pintype "passive"))
      (node (ref "P5") (pin "4") (pinfunction "4_4") (pintype "passive"))
      (node (ref "P6") (pin "2") (pinfunction "2_2") (pintype "passive"))
      (node (ref "Q1") (pin "1") (pinfunction "E_1") (pintype "passive"))
      (node (ref "Q2") (pin "1") (pinfunction "E_1") (pintype "passive"))
      (node (ref "R1") (pin "1") (pinfunction "1_1") (pintype "passive"))
      (node (ref "R10") (pin "2") (pinfunction "2_2") (pintype "passive"))
      (node (ref "R11") (pin "2") (pinfunction "2_2") (pintype "passive"))
      (node (ref "R2") (pin "1") (pinfunction "1_1") (pintype "passive"))
      (node (ref "R3") (pin "1") (pinfunction "1_1") (pintype "passive"))
      (node (ref "R4") (pin "1") (pinfunction "1_1") (pintype "passive"))
      (node (ref "R5") (pin "1") (pinfunction "1_1") (pintype "passive"))
      (node (ref "S4") (pin "1") (pinfunction "1_1") (pintype "passive"))
      (node (ref "S5") (pin "1") (pinfunction "1_1") (pintype "passive"))
      (node (ref "S6") (pin "1") (pinfunction "1_1") (pintype "passive"))
      (node (ref "U1") (pin "10") (pinfunction "GND_10") (pintype "passive"))
      (node (ref "U1") (pin "2") (pinfunction "E-_2") (pintype "passive"))
      (node (ref "U2") (pin "10") (pinfunction "GND_10") (pintype "passive"))
      (node (ref "U2") (pin "2") (pinfunction "E-_2") (pintype "passive"))
      (node (ref "U3") (pin "10") (pinfunction "GND_10") (pintype "passive"))
      (node (ref "U3") (pin "2") (pinfunction "E-_2") (pintype "passive"))
      (node (ref "U4") (pin "10") (pinfunction "GND_10") (pintype "passive"))
      (node (ref "U4") (pin "2") (pinfunction "E-_2") (pintype "passive"))
      (node (ref "U5") (pin "19") (pinfunction "GND_19") (pintype "passive"))
      (node (ref "U5") (pin "20") (pinfunction "GND_20") (pintype "passive"))
      (node (ref "U5") (pin "39") (pinfunction "GND_39") (pintype "passive"))
      (node (ref "U6") (pin "2") (pinfunction "GND_2") (pintype "passive"))
    )
    (net (code "62") (name "Net-(D1-K)") (class "Default")
      (node (ref "D1") (pin "2") (pinfunction "K_2") (pintype "passive"))
      (node (ref "R1") (pin "2") (pinfunction "2_2") (pintype "passive"))
    )
    (net (code "63") (name "Net-(D2-K)") (class "Default")
      (node (ref "D2") (pin "2") (pinfunction "K_2") (pintype "passive"))
      (node (ref "R2") (pin "2") (pinfunction "2_2") (pintype "passive"))
    )
    (net (code "64") (name "Net-(D3-K)") (class "Default")
      (node (ref "D3") (pin "2") (pinfunction "K_2") (pintype "passive"))
      (node (ref "R3") (pin "2") (pinfunction "2_2") (pintype "passive"))
    )
    (net (code "65") (name "Net-(D4-K)") (class "Default")
      (node (ref "D4") (pin "2") (pinfunction "K_2") (pintype "passive"))
      (node (ref "R4") (pin "2") (pinfunction "2_2") (pintype "passive"))
    )
    (net (code "66") (name "Net-(D5-K)") (class "Default")
      (node (ref "D5") (pin "2") (pinfunction "K_2") (pintype "passive"))
      (node (ref "R5") (pin "2") (pinfunction "2_2") (pintype "passive"))
    )
    (net (code "67") (name "Net-(D6-A)") (class "Default")
      (node (ref "D6") (pin "1") (pinfunction "A_1") (pintype "passive"))
      (node (ref "S1") (pin "2") (pinfunction "2_2") (pintype "passive"))
    )
    (net (code "68") (name "Net-(D7-K)") (class "Default")
      (node (ref "D7") (pin "2") (pinfunction "K_2") (pintype "passive"))
      (node (ref "S2") (pin "2") (pinfunction "2_2") (pintype "passive"))
    )
    (net (code "69") (name "Net-(D8-K)") (class "Default")
      (node (ref "D8") (pin "2") (pinfunction "K_2") (pintype "passive"))
      (node (ref "D9") (pin "2") (pinfunction "K_2") (pintype "passive"))
      (node (ref "S4") (pin "2") (pinfunction "2_2") (pintype "passive"))
    )
    (net (code "70") (name "Net-(LS1-B)") (class "Default")
      (node (ref "LS1") (pin "2") (pinfunction "B_2") (pintype "passive"))
      (node (ref "Q1") (pin "3") (pinfunction "C_3") (pintype "passive"))
    )
    (net (code "71") (name "Net-(Q1-B)") (class "Default")
      (node (ref "Q1") (pin "2") (pinfunction "B_2") (pintype "passive"))
      (node (ref "R10") (pin "1") (pinfunction "1_1") (pintype "passive"))
      (node (ref "R8") (pin "1") (pinfunction "1_1") (pintype "passive"))
    )
    (net (code "72") (name "Net-(Q2-B)") (class "Default")
      (node (ref "Q2") (pin "2") (pinfunction "B_2") (pintype "passive"))
      (node (ref "R11") (pin "1") (pinfunction "1_1") (pintype "passive"))
      (node (ref "R9") (pin "1") (pinfunction "1_1") (pintype "passive"))
    )
    (net (code "73") (name "Net-(Q2-C)") (class "Default")
      (node (ref "P4") (pin "2") (pinfunction "2_2") (pintype "passive"))
      (node (ref "Q2") (pin "3") (pinfunction "C_3") (pintype "passive"))
    )
    (net (code "74") (name "Net-(U7-K)") (class "Default")
      (node (ref "R12") (pin "2") (pinfunction "2_2") (pintype "passive"))
      (node (ref "U7") (pin "2") (pinfunction "K_2") (pintype "passive"))
    )
    (net (code "75") (name "Net-(U8-K)") (class "Default")
      (node (ref "R13") (pin "2") (pinfunction "2_2") (pintype "passive"))
      (node (ref "U8") (pin "2") (pinfunction "K_2") (pintype "passive"))
    )
    (net (code "76") (name "unconnected-(1-Pad1)") (class "Default")
      (node (ref "1") (pin "1") (pinfunction "1_1") (pintype "passive"))
    )
    (net (code "77") (name "unconnected-(2-Pad1)") (class "Default")
      (node (ref "2") (pin "1") (pinfunction "1_1") (pintype "passive"))
    )
    (net (code "78") (name "unconnected-(3-Pad1)") (class "Default")
      (node (ref "3") (pin "1") (pinfunction "1_1") (pintype "passive"))
    )
    (net (code "79") (name "unconnected-(4-Pad1)") (class "Default")
      (node (ref "4") (pin "1") (pinfunction "1_1") (pintype "passive"))
    )
    (net (code "80") (name "unconnected-(5-Pad1)") (class "Default")
      (node (ref "5") (pin "1") (pinfunction "1_1") (pintype "passive"))
    )
    (net (code "81") (name "unconnected-(6-Pad1)") (class "Default")
      (node (ref "6") (pin "1") (pinfunction "1_1") (pintype "passive"))
    )
    (net (code "82") (name "unconnected-(7-Pad1)") (class "Default")
      (node (ref "7") (pin "1") (pinfunction "1_1") (pintype "passive"))
    )
    (net (code "83") (name "unconnected-(8-Pad1)") (class "Default")
      (node (ref "8") (pin "1") (pinfunction "1_1") (pintype "passive"))
    )
    (net (code "84") (name "unconnected-(J1-MH1-Pad16)") (class "Default")
      (node (ref "J1") (pin "16") (pinfunction "MH1_16") (pintype "passive"))
    )
    (net (code "85") (name "unconnected-(J1-MH2-Pad17)") (class "Default")
      (node (ref "J1") (pin "17") (pinfunction "MH2_17") (pintype "passive"))
    )
    (net (code "86") (name "unconnected-(U5-B5-Pad33)") (class "Default")
      (node (ref "U5") (pin "33") (pinfunction "B5_33") (pintype "passive"))
    )
    (net (code "87") (name "unconnected-(U5-C13-Pad2)") (class "Default")
      (node (ref "U5") (pin "2") (pinfunction "C13_2") (pintype "passive"))
    )
    (net (code "88") (name "unconnected-(U5-C14-Pad3)") (class "Default")
      (node (ref "U5") (pin "3") (pinfunction "C14_3") (pintype "passive"))
    )
    (net (code "89") (name "unconnected-(U5-C15-Pad4)") (class "Default")
      (node (ref "U5") (pin "4") (pinfunction "C15_4") (pintype "passive"))
    )
    (net (code "90") (name "unconnected-(U5-FT_A11-Pad28)") (class "Default")
      (node (ref "U5") (pin "28") (pinfunction "FT_A11_28") (pintype "passive"))
    )
    (net (code "91") (name "unconnected-(U5-FT_A12-Pad29)") (class "Default")
      (node (ref "U5") (pin "29") (pinfunction "FT_A12_29") (pintype "passive"))
    )
    (net (code "92") (name "unconnected-(U5-NRST-Pad17)") (class "Default")
      (node (ref "U5") (pin "17") (pinfunction "NRST_17") (pintype "passive"))
    )
    (net (code "93") (name "unconnected-(U5-VBAT-Pad1)") (class "Default")
      (node (ref "U5") (pin "1") (pinfunction "VBAT_1") (pintype "passive"))
    )
    (net (code "94") (name "unconnected-(U6-EARL-Pad22)") (class "Default")
      (node (ref "U6") (pin "22") (pinfunction "EARL_22") (pintype "passive"))
    )
    (net (code "95") (name "unconnected-(U6-EARR-Pad23)") (class "Default")
      (node (ref "U6") (pin "23") (pinfunction "EARR_23") (pintype "passive"))
    )
    (net (code "96") (name "unconnected-(U6-GND-Pad14)") (class "Default")
      (node (ref "U6") (pin "14") (pinfunction "GND_14") (pintype "passive"))
    )
    (net (code "97") (name "unconnected-(U6-GPIO1-Pad10)") (class "Default")
      (node (ref "U6") (pin "10") (pinfunction "GPIO1_10") (pintype "passive"))
    )
    (net (code "98") (name "unconnected-(U6-GPIO14-Pad16)") (class "Default")
      (node (ref "U6") (pin "16") (pinfunction "GPIO14_16") (pintype "passive"))
    )
    (net (code "99") (name "unconnected-(U6-GPIO15-Pad17)") (class "Default")
      (node (ref "U6") (pin "17") (pinfunction "GPIO15_17") (pintype "passive"))
    )
    (net (code "100") (name "unconnected-(U6-GPIO16-Pad18)") (class "Default")
      (node (ref "U6") (pin "18") (pinfunction "GPIO16_18") (pintype "passive"))
    )
    (net (code "101") (name "unconnected-(U6-HRXD-Pad21)") (class "Default")
      (node (ref "U6") (pin "21") (pinfunction "HRXD_21") (pintype "passive"))
    )
    (net (code "102") (name "unconnected-(U6-HTXD-Pad20)") (class "Default")
      (node (ref "U6") (pin "20") (pinfunction "HTXD_20") (pintype "passive"))
    )
    (net (code "103") (name "unconnected-(U6-MIC+-Pad4)") (class "Default")
      (node (ref "U6") (pin "4") (pinfunction "MIC+_4") (pintype "passive"))
    )
    (net (code "104") (name "unconnected-(U6-MIC--Pad3)") (class "Default")
      (node (ref "U6") (pin "3") (pinfunction "MIC-_3") (pintype "passive"))
    )
    (net (code "105") (name "unconnected-(U6-MIC2P-Pad5)") (class "Default")
      (node (ref "U6") (pin "5") (pinfunction "MIC2P_5") (pintype "passive"))
    )
    (net (code "106") (name "unconnected-(U6-NC-Pad15)") (class "Default")
      (node (ref "U6") (pin "15") (pinfunction "NC_15") (pintype "passive"))
    )
    (net (code "107") (name "unconnected-(U6-REC+-Pad6)") (class "Default")
      (node (ref "U6") (pin "6") (pinfunction "REC+_6") (pintype "passive"))
    )
    (net (code "108") (name "unconnected-(U6-REC--Pad7)") (class "Default")
      (node (ref "U6") (pin "7") (pinfunction "REC-_7") (pintype "passive"))
    )
    (net (code "109") (name "unconnected-(U6-UCTS-Pad12)") (class "Default")
      (node (ref "U6") (pin "12") (pinfunction "UCTS_12") (pintype "passive"))
    )
    (net (code "110") (name "unconnected-(U6-URTS-Pad11)") (class "Default")
      (node (ref "U6") (pin "11") (pinfunction "URTS_11") (pintype "passive"))
    )
  )
)
